# ecm.net
KiCad netlist of a schematic drawn in EAGLE
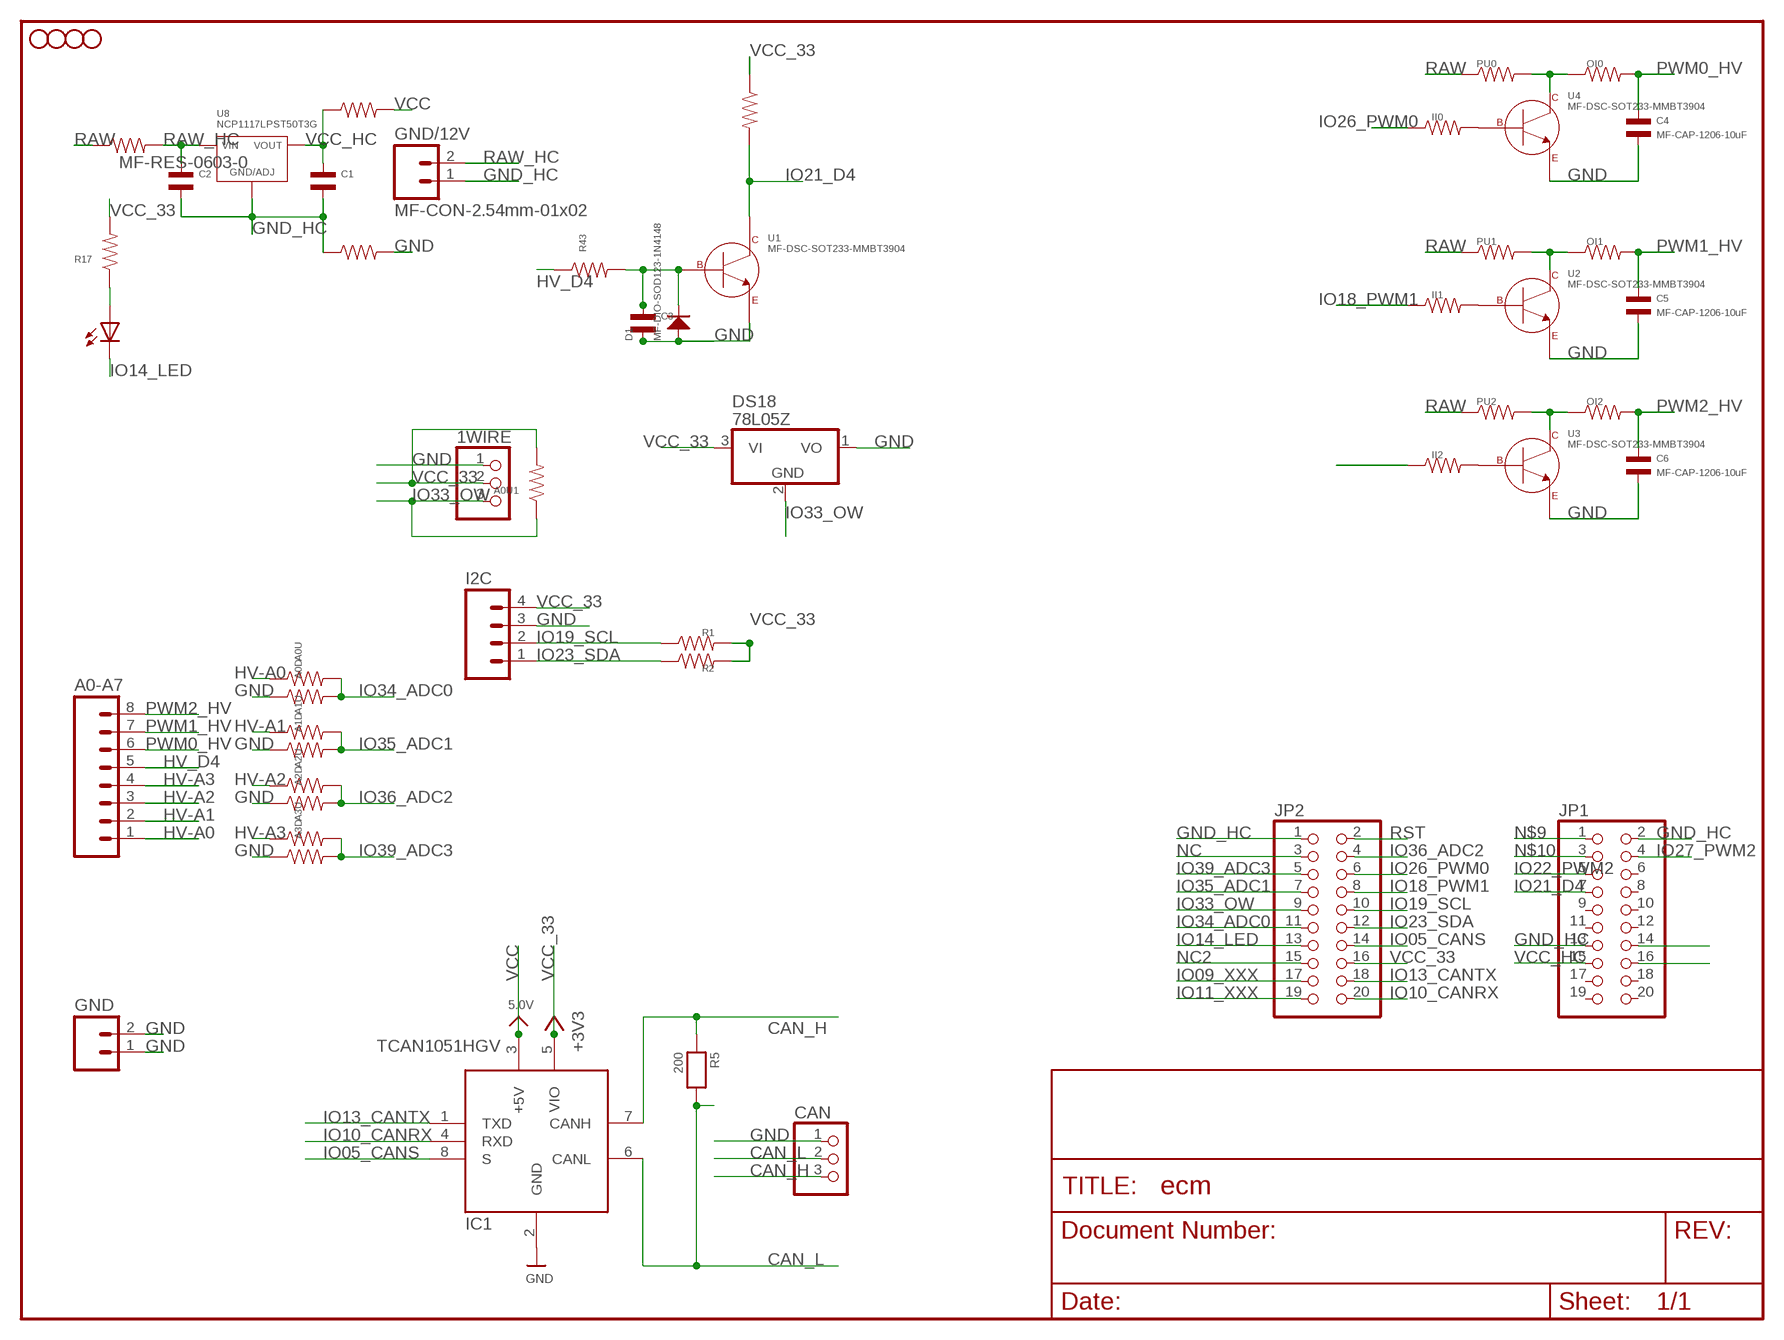
[diagram p0: schematic, sheet 1]

(export (version "E")
  (design (tool "Eeschema 10.0.6"))
  (components
    (comp (ref "1WIRE")
      (value "1WIRE")
      (footprint "eagle-import:1X03")
      (libsource (lib "eagle-import") (part "PINHD-1X3"))
    )
    (comp (ref "A0-A7")
      (value "MF-CON-2.54mm-01x08")
      (footprint "eagle-import:1X08")
      (libsource (lib "eagle-import") (part "M081X08"))
    )
    (comp (ref "A0D")
      (value "RESISTOR_1206")
      (footprint "eagle-import:R1206")
      (libsource (lib "eagle-import") (part "RESISTOR_1206"))
    )
    (comp (ref "A0U")
      (value "RESISTOR_1206")
      (footprint "eagle-import:R1206")
      (libsource (lib "eagle-import") (part "RESISTOR_1206"))
    )
    (comp (ref "A0U1")
      (value "RESISTOR_1206")
      (footprint "eagle-import:R1206")
      (libsource (lib "eagle-import") (part "RESISTOR_1206"))
    )
    (comp (ref "A1D")
      (value "RESISTOR_1206")
      (footprint "eagle-import:R1206")
      (libsource (lib "eagle-import") (part "RESISTOR_1206"))
    )
    (comp (ref "A1U")
      (value "RESISTOR_1206")
      (footprint "eagle-import:R1206")
      (libsource (lib "eagle-import") (part "RESISTOR_1206"))
    )
    (comp (ref "A2D")
      (value "RESISTOR_1206")
      (footprint "eagle-import:R1206")
      (libsource (lib "eagle-import") (part "RESISTOR_1206"))
    )
    (comp (ref "A2U")
      (value "RESISTOR_1206")
      (footprint "eagle-import:R1206")
      (libsource (lib "eagle-import") (part "RESISTOR_1206"))
    )
    (comp (ref "A3D")
      (value "RESISTOR_1206")
      (footprint "eagle-import:R1206")
      (libsource (lib "eagle-import") (part "RESISTOR_1206"))
    )
    (comp (ref "A3U")
      (value "RESISTOR_1206")
      (footprint "eagle-import:R1206")
      (libsource (lib "eagle-import") (part "RESISTOR_1206"))
    )
    (comp (ref "C1")
      (value "CAPACITOR_NP_1210")
      (footprint "eagle-import:C1210")
      (libsource (lib "eagle-import") (part "CAPACITOR_NP_1210"))
    )
    (comp (ref "C2")
      (value "CAPACITOR_NP_1210")
      (footprint "eagle-import:C1210")
      (libsource (lib "eagle-import") (part "CAPACITOR_NP_1210"))
    )
    (comp (ref "C3")
      (value "CAPACITOR_NP_1210")
      (footprint "eagle-import:C1210")
      (libsource (lib "eagle-import") (part "CAPACITOR_NP_1210"))
    )
    (comp (ref "C4")
      (value "MF-CAP-1206-10uF")
      (footprint "eagle-import:C1206")
      (libsource (lib "eagle-import") (part "CAPACITOR_NP_1206"))
    )
    (comp (ref "C5")
      (value "MF-CAP-1206-10uF")
      (footprint "eagle-import:C1206")
      (libsource (lib "eagle-import") (part "CAPACITOR_NP_1206"))
    )
    (comp (ref "C6")
      (value "MF-CAP-1206-10uF")
      (footprint "eagle-import:C1206")
      (libsource (lib "eagle-import") (part "CAPACITOR_NP_1206"))
    )
    (comp (ref "CAN")
      (value "PINHD-1X3")
      (footprint "eagle-import:1X03")
      (libsource (lib "eagle-import") (part "PINHD-1X3"))
    )
    (comp (ref "D1")
      (value "MF-DIO-SOD123-1N4148")
      (footprint "eagle-import:SOD-123")
      (fields (field (name "HOUSEPART") "YES"))
      (libsource (lib "eagle-import") (part "DIODES_SOD-123_1N4148"))
    )
    (comp (ref "D2")
      (value "RED")
      (footprint "eagle-import:LED-1206")
      (libsource (lib "eagle-import") (part "LED-RED1206"))
    )
    (comp (ref "DS18")
      (value "78L05Z")
      (footprint "eagle-import:TO92")
      (libsource (lib "eagle-import") (part "78ZL05"))
    )
    (comp (ref "GND")
      (value "MF-CON-2.54mm-01x02")
      (footprint "eagle-import:1X02")
      (libsource (lib "eagle-import") (part "M02PTH"))
    )
    (comp (ref "GND/12V")
      (value "MF-CON-2.54mm-01x02")
      (footprint "eagle-import:1X02")
      (libsource (lib "eagle-import") (part "M02PTH"))
    )
    (comp (ref "I2C")
      (value "PPPC041LFBN-RC")
      (footprint "eagle-import:1X04")
      (libsource (lib "eagle-import") (part "M04PTH"))
    )
    (comp (ref "IC1")
      (value "TCAN1051HGV")
      (footprint "eagle-import:SOIC8_150MIL")
      (libsource (lib "eagle-import") (part "CAN_TRANSCIEVER_TCAN1051V"))
    )
    (comp (ref "II0")
      (value "RESISTOR_1206")
      (footprint "eagle-import:R1206")
      (libsource (lib "eagle-import") (part "RESISTOR_1206"))
    )
    (comp (ref "II1")
      (value "RESISTOR_1206")
      (footprint "eagle-import:R1206")
      (libsource (lib "eagle-import") (part "RESISTOR_1206"))
    )
    (comp (ref "II2")
      (value "RESISTOR_1206")
      (footprint "eagle-import:R1206")
      (libsource (lib "eagle-import") (part "RESISTOR_1206"))
    )
    (comp (ref "JP1")
      (value "HEADER-2X10")
      (footprint "eagle-import:2X10")
      (libsource (lib "eagle-import") (part "HEADER-2X10"))
    )
    (comp (ref "JP2")
      (value "HEADER-2X10")
      (footprint "eagle-import:2X10")
      (libsource (lib "eagle-import") (part "HEADER-2X10"))
    )
    (comp (ref "OI0")
      (value "RESISTOR_1206")
      (footprint "eagle-import:R1206")
      (libsource (lib "eagle-import") (part "RESISTOR_1206"))
    )
    (comp (ref "OI1")
      (value "RESISTOR_1206")
      (footprint "eagle-import:R1206")
      (libsource (lib "eagle-import") (part "RESISTOR_1206"))
    )
    (comp (ref "OI2")
      (value "RESISTOR_1206")
      (footprint "eagle-import:R1206")
      (libsource (lib "eagle-import") (part "RESISTOR_1206"))
    )
    (comp (ref "PU0")
      (value "RESISTOR_1206")
      (footprint "eagle-import:R1206")
      (libsource (lib "eagle-import") (part "RESISTOR_1206"))
    )
    (comp (ref "PU1")
      (value "RESISTOR_1206")
      (footprint "eagle-import:R1206")
      (libsource (lib "eagle-import") (part "RESISTOR_1206"))
    )
    (comp (ref "PU2")
      (value "RESISTOR_1206")
      (footprint "eagle-import:R1206")
      (libsource (lib "eagle-import") (part "RESISTOR_1206"))
    )
    (comp (ref "R1")
      (value "RESISTOR_1206")
      (footprint "eagle-import:R1206")
      (libsource (lib "eagle-import") (part "RESISTOR_1206"))
    )
    (comp (ref "R2")
      (value "RESISTOR_1206")
      (footprint "eagle-import:R1206")
      (libsource (lib "eagle-import") (part "RESISTOR_1206"))
    )
    (comp (ref "R5")
      (value "200")
      (footprint "eagle-import:1206")
      (libsource (lib "eagle-import") (part "microbuilder_RESISTOR1206"))
    )
    (comp (ref "R17")
      (value "RESISTOR_1206")
      (footprint "eagle-import:R1206")
      (libsource (lib "eagle-import") (part "RESISTOR_1206"))
    )
    (comp (ref "R43")
      (value "RESISTOR_1206")
      (footprint "eagle-import:R1206")
      (libsource (lib "eagle-import") (part "RESISTOR_1206"))
    )
    (comp (ref "R45")
      (value "RESISTOR_1206")
      (footprint "eagle-import:R1206")
      (libsource (lib "eagle-import") (part "RESISTOR_1206"))
    )
    (comp (ref "RIN7")
      (value "MF-RES-0603-0")
      (footprint "eagle-import:1206")
      (libsource (lib "eagle-import") (part "RESISTOR1206"))
    )
    (comp (ref "RIN8")
      (value "MF-RES-0603-0")
      (footprint "eagle-import:1206")
      (libsource (lib "eagle-import") (part "RESISTOR1206"))
    )
    (comp (ref "RIN19")
      (value "MF-RES-0603-0")
      (footprint "eagle-import:1206")
      (libsource (lib "eagle-import") (part "RESISTOR1206"))
    )
    (comp (ref "STANDOFF2")
      (value "STAND-OFF")
      (footprint "eagle-import:STAND-OFF")
      (libsource (lib "eagle-import") (part "STAND-OFF"))
    )
    (comp (ref "STANDOFF3")
      (value "STAND-OFF")
      (footprint "eagle-import:STAND-OFF")
      (libsource (lib "eagle-import") (part "STAND-OFF"))
    )
    (comp (ref "STANDOFF4")
      (value "STAND-OFF")
      (footprint "eagle-import:STAND-OFF")
      (libsource (lib "eagle-import") (part "STAND-OFF"))
    )
    (comp (ref "STANDOFF5")
      (value "STAND-OFF")
      (footprint "eagle-import:STAND-OFF")
      (libsource (lib "eagle-import") (part "STAND-OFF"))
    )
    (comp (ref "U1")
      (value "MF-DSC-SOT233-MMBT3904")
      (footprint "eagle-import:SOT-23-3")
      (fields (field (name "HOUSEPART") "YES"))
      (libsource (lib "eagle-import") (part "NPN_BJT_SOT-23-3MMBT3904"))
    )
    (comp (ref "U2")
      (value "MF-DSC-SOT233-MMBT3904")
      (footprint "eagle-import:SOT-23-3")
      (fields (field (name "HOUSEPART") "YES"))
      (libsource (lib "eagle-import") (part "NPN_BJT_SOT-23-3MMBT3904"))
    )
    (comp (ref "U3")
      (value "MF-DSC-SOT233-MMBT3904")
      (footprint "eagle-import:SOT-23-3")
      (fields (field (name "HOUSEPART") "YES"))
      (libsource (lib "eagle-import") (part "NPN_BJT_SOT-23-3MMBT3904"))
    )
    (comp (ref "U4")
      (value "MF-DSC-SOT233-MMBT3904")
      (footprint "eagle-import:SOT-23-3")
      (fields (field (name "HOUSEPART") "YES"))
      (libsource (lib "eagle-import") (part "NPN_BJT_SOT-23-3MMBT3904"))
    )
    (comp (ref "U8")
      (value "NCP1117LPST50T3G")
      (footprint "eagle-import:SOT-223-3")
      (fields (field (name "HOUSEPART") "NO"))
      (libsource (lib "eagle-import") (part "NCP1117LPST50T3G"))
    )
  )
  (nets
    (net (code "1") (name "+3V3") (class "Default")
      (node (ref "1WIRE") (pin "2") (pinfunction "2_2") (pintype "passive"))
      (node (ref "A0U1") (pin "P$2") (pinfunction "P$2_P$2") (pintype "passive"))
      (node (ref "DS18") (pin "3") (pinfunction "VI_3") (pintype "input"))
      (node (ref "I2C") (pin "4") (pinfunction "4_4") (pintype "passive"))
      (node (ref "IC1") (pin "5") (pinfunction "VIO_5") (pintype "power_in"))
      (node (ref "JP2") (pin "16") (pinfunction "16_16") (pintype "passive"))
      (node (ref "R1") (pin "P$2") (pinfunction "P$2_P$2") (pintype "passive"))
      (node (ref "R17") (pin "P$2") (pinfunction "P$2_P$2") (pintype "passive"))
      (node (ref "R2") (pin "P$2") (pinfunction "P$2_P$2") (pintype "passive"))
      (node (ref "R45") (pin "P$1") (pinfunction "P$1_P$1") (pintype "passive"))
    )
    (net (code "2") (name "/CAN_H") (class "Default")
      (node (ref "CAN") (pin "3") (pinfunction "3_3") (pintype "passive"))
      (node (ref "IC1") (pin "7") (pinfunction "CANH_7") (pintype "bidirectional"))
      (node (ref "R5") (pin "1") (pinfunction "1_1") (pintype "passive"))
    )
    (net (code "3") (name "/CAN_L") (class "Default")
      (node (ref "CAN") (pin "2") (pinfunction "2_2") (pintype "passive"))
      (node (ref "IC1") (pin "6") (pinfunction "CANL_6") (pintype "bidirectional"))
      (node (ref "R5") (pin "2") (pinfunction "2_2") (pintype "passive"))
    )
    (net (code "4") (name "/GND_HC") (class "Default")
      (node (ref "C1") (pin "P$2") (pinfunction "P$2_P$2") (pintype "passive"))
      (node (ref "C2") (pin "P$2") (pinfunction "P$2_P$2") (pintype "passive"))
      (node (ref "GND/12V") (pin "1") (pinfunction "1_1") (pintype "passive"))
      (node (ref "JP1") (pin "13") (pinfunction "13_13") (pintype "passive"))
      (node (ref "JP1") (pin "2") (pinfunction "2_2") (pintype "passive"))
      (node (ref "JP2") (pin "1") (pinfunction "1_1") (pintype "passive"))
      (node (ref "RIN8") (pin "1") (pinfunction "1_1") (pintype "passive"))
      (node (ref "U8") (pin "P$2") (pinfunction "GND/ADJ_P$2") (pintype "bidirectional"))
    )
    (net (code "5") (name "/HV-A0") (class "Default")
      (node (ref "A0-A7") (pin "1") (pinfunction "1_1") (pintype "passive"))
      (node (ref "A0U") (pin "P$1") (pinfunction "P$1_P$1") (pintype "passive"))
    )
    (net (code "6") (name "/HV-A1") (class "Default")
      (node (ref "A0-A7") (pin "2") (pinfunction "2_2") (pintype "passive"))
      (node (ref "A1U") (pin "P$1") (pinfunction "P$1_P$1") (pintype "passive"))
    )
    (net (code "7") (name "/HV-A2") (class "Default")
      (node (ref "A0-A7") (pin "3") (pinfunction "3_3") (pintype "passive"))
      (node (ref "A2U") (pin "P$1") (pinfunction "P$1_P$1") (pintype "passive"))
    )
    (net (code "8") (name "/HV-A3") (class "Default")
      (node (ref "A0-A7") (pin "4") (pinfunction "4_4") (pintype "passive"))
      (node (ref "A3U") (pin "P$1") (pinfunction "P$1_P$1") (pintype "passive"))
    )
    (net (code "9") (name "/HV_D4") (class "Default")
      (node (ref "A0-A7") (pin "5") (pinfunction "5_5") (pintype "passive"))
      (node (ref "R43") (pin "P$1") (pinfunction "P$1_P$1") (pintype "passive"))
    )
    (net (code "10") (name "/IO05_CANS") (class "Default")
      (node (ref "IC1") (pin "8") (pinfunction "S_8") (pintype "input"))
      (node (ref "JP2") (pin "14") (pinfunction "14_14") (pintype "passive"))
    )
    (net (code "11") (name "/IO09_XXX") (class "Default")
      (node (ref "JP2") (pin "17") (pinfunction "17_17") (pintype "passive"))
    )
    (net (code "12") (name "/IO10_CANRX") (class "Default")
      (node (ref "IC1") (pin "4") (pinfunction "RXD_4") (pintype "output"))
      (node (ref "JP2") (pin "20") (pinfunction "20_20") (pintype "passive"))
    )
    (net (code "13") (name "/IO11_XXX") (class "Default")
      (node (ref "JP2") (pin "19") (pinfunction "19_19") (pintype "passive"))
    )
    (net (code "14") (name "/IO13_CANTX") (class "Default")
      (node (ref "IC1") (pin "1") (pinfunction "TXD_1") (pintype "input"))
      (node (ref "JP2") (pin "18") (pinfunction "18_18") (pintype "passive"))
    )
    (net (code "15") (name "/IO14_LED") (class "Default")
      (node (ref "D2") (pin "C") (pinfunction "C_C") (pintype "passive"))
      (node (ref "JP2") (pin "13") (pinfunction "13_13") (pintype "passive"))
    )
    (net (code "16") (name "/IO18_PWM1") (class "Default")
      (node (ref "II1") (pin "P$1") (pinfunction "P$1_P$1") (pintype "passive"))
      (node (ref "JP2") (pin "8") (pinfunction "8_8") (pintype "passive"))
    )
    (net (code "17") (name "/IO19_SCL") (class "Default")
      (node (ref "I2C") (pin "2") (pinfunction "2_2") (pintype "passive"))
      (node (ref "JP2") (pin "10") (pinfunction "10_10") (pintype "passive"))
      (node (ref "R1") (pin "P$1") (pinfunction "P$1_P$1") (pintype "passive"))
    )
    (net (code "18") (name "/IO21_D4") (class "Default")
      (node (ref "JP1") (pin "7") (pinfunction "7_7") (pintype "passive"))
      (node (ref "R45") (pin "P$2") (pinfunction "P$2_P$2") (pintype "passive"))
      (node (ref "U1") (pin "P$3") (pinfunction "COLLECTOR_P$3") (pintype "bidirectional"))
    )
    (net (code "19") (name "/IO22_PWM2") (class "Default")
      (node (ref "II2") (pin "P$1") (pinfunction "P$1_P$1") (pintype "passive"))
      (node (ref "JP1") (pin "5") (pinfunction "5_5") (pintype "passive"))
    )
    (net (code "20") (name "/IO23_SDA") (class "Default")
      (node (ref "I2C") (pin "1") (pinfunction "1_1") (pintype "passive"))
      (node (ref "JP2") (pin "12") (pinfunction "12_12") (pintype "passive"))
      (node (ref "R2") (pin "P$1") (pinfunction "P$1_P$1") (pintype "passive"))
    )
    (net (code "21") (name "/IO26_PWM0") (class "Default")
      (node (ref "II0") (pin "P$1") (pinfunction "P$1_P$1") (pintype "passive"))
      (node (ref "JP2") (pin "6") (pinfunction "6_6") (pintype "passive"))
    )
    (net (code "22") (name "/IO27_PWM2") (class "Default")
      (node (ref "JP1") (pin "4") (pinfunction "4_4") (pintype "passive"))
    )
    (net (code "23") (name "/IO33_OW") (class "Default")
      (node (ref "1WIRE") (pin "3") (pinfunction "3_3") (pintype "passive"))
      (node (ref "A0U1") (pin "P$1") (pinfunction "P$1_P$1") (pintype "passive"))
      (node (ref "DS18") (pin "2") (pinfunction "GND_2") (pintype "passive"))
      (node (ref "JP2") (pin "9") (pinfunction "9_9") (pintype "passive"))
    )
    (net (code "24") (name "/IO34_ADC0") (class "Default")
      (node (ref "A0D") (pin "P$2") (pinfunction "P$2_P$2") (pintype "passive"))
      (node (ref "A0U") (pin "P$2") (pinfunction "P$2_P$2") (pintype "passive"))
      (node (ref "JP2") (pin "11") (pinfunction "11_11") (pintype "passive"))
    )
    (net (code "25") (name "/IO35_ADC1") (class "Default")
      (node (ref "A1D") (pin "P$2") (pinfunction "P$2_P$2") (pintype "passive"))
      (node (ref "A1U") (pin "P$2") (pinfunction "P$2_P$2") (pintype "passive"))
      (node (ref "JP2") (pin "7") (pinfunction "7_7") (pintype "passive"))
    )
    (net (code "26") (name "/IO36_ADC2") (class "Default")
      (node (ref "A2D") (pin "P$2") (pinfunction "P$2_P$2") (pintype "passive"))
      (node (ref "A2U") (pin "P$2") (pinfunction "P$2_P$2") (pintype "passive"))
      (node (ref "JP2") (pin "4") (pinfunction "4_4") (pintype "passive"))
    )
    (net (code "27") (name "/IO39_ADC3") (class "Default")
      (node (ref "A3D") (pin "P$2") (pinfunction "P$2_P$2") (pintype "passive"))
      (node (ref "A3U") (pin "P$2") (pinfunction "P$2_P$2") (pintype "passive"))
      (node (ref "JP2") (pin "5") (pinfunction "5_5") (pintype "passive"))
    )
    (net (code "28") (name "/N$9") (class "Default")
      (node (ref "JP1") (pin "1") (pinfunction "1_1") (pintype "passive"))
    )
    (net (code "29") (name "/N$10") (class "Default")
      (node (ref "JP1") (pin "3") (pinfunction "3_3") (pintype "passive"))
    )
    (net (code "30") (name "/NC") (class "Default")
      (node (ref "JP2") (pin "3") (pinfunction "3_3") (pintype "passive"))
    )
    (net (code "31") (name "/NC2") (class "Default")
      (node (ref "JP2") (pin "15") (pinfunction "15_15") (pintype "passive"))
    )
    (net (code "32") (name "/PWM0_HV") (class "Default")
      (node (ref "A0-A7") (pin "6") (pinfunction "6_6") (pintype "passive"))
      (node (ref "C4") (pin "P$1") (pinfunction "P$1_P$1") (pintype "passive"))
      (node (ref "OI0") (pin "P$2") (pinfunction "P$2_P$2") (pintype "passive"))
    )
    (net (code "33") (name "/PWM1_HV") (class "Default")
      (node (ref "A0-A7") (pin "7") (pinfunction "7_7") (pintype "passive"))
      (node (ref "C5") (pin "P$1") (pinfunction "P$1_P$1") (pintype "passive"))
      (node (ref "OI1") (pin "P$2") (pinfunction "P$2_P$2") (pintype "passive"))
    )
    (net (code "34") (name "/PWM2_HV") (class "Default")
      (node (ref "A0-A7") (pin "8") (pinfunction "8_8") (pintype "passive"))
      (node (ref "C6") (pin "P$1") (pinfunction "P$1_P$1") (pintype "passive"))
      (node (ref "OI2") (pin "P$2") (pinfunction "P$2_P$2") (pintype "passive"))
    )
    (net (code "35") (name "/RAW") (class "Default")
      (node (ref "PU0") (pin "P$1") (pinfunction "P$1_P$1") (pintype "passive"))
      (node (ref "PU1") (pin "P$1") (pinfunction "P$1_P$1") (pintype "passive"))
      (node (ref "PU2") (pin "P$1") (pinfunction "P$1_P$1") (pintype "passive"))
      (node (ref "RIN19") (pin "1") (pinfunction "1_1") (pintype "passive"))
    )
    (net (code "36") (name "/RAW_HC") (class "Default")
      (node (ref "C2") (pin "P$1") (pinfunction "P$1_P$1") (pintype "passive"))
      (node (ref "GND/12V") (pin "2") (pinfunction "2_2") (pintype "passive"))
      (node (ref "RIN19") (pin "2") (pinfunction "2_2") (pintype "passive"))
      (node (ref "U8") (pin "P$4") (pinfunction "VIN_P$4") (pintype "bidirectional"))
    )
    (net (code "37") (name "/RST") (class "Default")
      (node (ref "JP2") (pin "2") (pinfunction "2_2") (pintype "passive"))
    )
    (net (code "38") (name "/VCC_HC") (class "Default")
      (node (ref "C1") (pin "P$1") (pinfunction "P$1_P$1") (pintype "passive"))
      (node (ref "JP1") (pin "15") (pinfunction "15_15") (pintype "passive"))
      (node (ref "RIN7") (pin "1") (pinfunction "1_1") (pintype "passive"))
      (node (ref "U8") (pin "P$1") (pinfunction "VOUT_P$1") (pintype "bidirectional"))
      (node (ref "U8") (pin "P$3") (pinfunction "VOUT_P$3") (pintype "bidirectional"))
    )
    (net (code "39") (name "5.0V") (class "Default")
      (node (ref "IC1") (pin "3") (pinfunction "+5V_3") (pintype "power_in"))
      (node (ref "RIN7") (pin "2") (pinfunction "2_2") (pintype "passive"))
    )
    (net (code "40") (name "GND") (class "Default")
      (node (ref "1WIRE") (pin "1") (pinfunction "1_1") (pintype "passive"))
      (node (ref "A0D") (pin "P$1") (pinfunction "P$1_P$1") (pintype "passive"))
      (node (ref "A1D") (pin "P$1") (pinfunction "P$1_P$1") (pintype "passive"))
      (node (ref "A2D") (pin "P$1") (pinfunction "P$1_P$1") (pintype "passive"))
      (node (ref "A3D") (pin "P$1") (pinfunction "P$1_P$1") (pintype "passive"))
      (node (ref "C3") (pin "P$2") (pinfunction "P$2_P$2") (pintype "passive"))
      (node (ref "C4") (pin "P$2") (pinfunction "P$2_P$2") (pintype "passive"))
      (node (ref "C5") (pin "P$2") (pinfunction "P$2_P$2") (pintype "passive"))
      (node (ref "C6") (pin "P$2") (pinfunction "P$2_P$2") (pintype "passive"))
      (node (ref "CAN") (pin "1") (pinfunction "1_1") (pintype "passive"))
      (node (ref "D1") (pin "ANODE") (pinfunction "ANODE_ANODE") (pintype "bidirectional"))
      (node (ref "DS18") (pin "1") (pinfunction "VO_1") (pintype "passive"))
      (node (ref "GND") (pin "1") (pinfunction "1_1") (pintype "passive"))
      (node (ref "GND") (pin "2") (pinfunction "2_2") (pintype "passive"))
      (node (ref "I2C") (pin "3") (pinfunction "3_3") (pintype "passive"))
      (node (ref "IC1") (pin "2") (pinfunction "GND_2") (pintype "power_in"))
      (node (ref "RIN8") (pin "2") (pinfunction "2_2") (pintype "passive"))
      (node (ref "U1") (pin "P$2") (pinfunction "EMITTER_P$2") (pintype "bidirectional"))
      (node (ref "U2") (pin "P$2") (pinfunction "EMITTER_P$2") (pintype "bidirectional"))
      (node (ref "U3") (pin "P$2") (pinfunction "EMITTER_P$2") (pintype "bidirectional"))
      (node (ref "U4") (pin "P$2") (pinfunction "EMITTER_P$2") (pintype "bidirectional"))
    )
    (net (code "41") (name "Net-(D2-PadA)") (class "Default")
      (node (ref "D2") (pin "A") (pinfunction "A_A") (pintype "passive"))
      (node (ref "R17") (pin "P$1") (pinfunction "P$1_P$1") (pintype "passive"))
    )
    (net (code "42") (name "Net-(U1-BASE)") (class "Default")
      (node (ref "C3") (pin "P$1") (pinfunction "P$1_P$1") (pintype "passive"))
      (node (ref "D1") (pin "CATHODE") (pinfunction "CATHODE_CATHODE") (pintype "bidirectional"))
      (node (ref "R43") (pin "P$2") (pinfunction "P$2_P$2") (pintype "passive"))
      (node (ref "U1") (pin "P$1") (pinfunction "BASE_P$1") (pintype "bidirectional"))
    )
    (net (code "43") (name "Net-(U2-BASE)") (class "Default")
      (node (ref "II1") (pin "P$2") (pinfunction "P$2_P$2") (pintype "passive"))
      (node (ref "U2") (pin "P$1") (pinfunction "BASE_P$1") (pintype "bidirectional"))
    )
    (net (code "44") (name "Net-(U2-COLLECTOR)") (class "Default")
      (node (ref "OI1") (pin "P$1") (pinfunction "P$1_P$1") (pintype "passive"))
      (node (ref "PU1") (pin "P$2") (pinfunction "P$2_P$2") (pintype "passive"))
      (node (ref "U2") (pin "P$3") (pinfunction "COLLECTOR_P$3") (pintype "bidirectional"))
    )
    (net (code "45") (name "Net-(U3-BASE)") (class "Default")
      (node (ref "II2") (pin "P$2") (pinfunction "P$2_P$2") (pintype "passive"))
      (node (ref "U3") (pin "P$1") (pinfunction "BASE_P$1") (pintype "bidirectional"))
    )
    (net (code "46") (name "Net-(U3-COLLECTOR)") (class "Default")
      (node (ref "OI2") (pin "P$1") (pinfunction "P$1_P$1") (pintype "passive"))
      (node (ref "PU2") (pin "P$2") (pinfunction "P$2_P$2") (pintype "passive"))
      (node (ref "U3") (pin "P$3") (pinfunction "COLLECTOR_P$3") (pintype "bidirectional"))
    )
    (net (code "47") (name "Net-(U4-BASE)") (class "Default")
      (node (ref "II0") (pin "P$2") (pinfunction "P$2_P$2") (pintype "passive"))
      (node (ref "U4") (pin "P$1") (pinfunction "BASE_P$1") (pintype "bidirectional"))
    )
    (net (code "48") (name "Net-(U4-COLLECTOR)") (class "Default")
      (node (ref "OI0") (pin "P$1") (pinfunction "P$1_P$1") (pintype "passive"))
      (node (ref "PU0") (pin "P$2") (pinfunction "P$2_P$2") (pintype "passive"))
      (node (ref "U4") (pin "P$3") (pinfunction "COLLECTOR_P$3") (pintype "bidirectional"))
    )
    (net (code "49") (name "unconnected-(JP1-Pad6)") (class "Default")
      (node (ref "JP1") (pin "6") (pinfunction "6_6") (pintype "passive"))
    )
    (net (code "50") (name "unconnected-(JP1-Pad8)") (class "Default")
      (node (ref "JP1") (pin "8") (pinfunction "8_8") (pintype "passive"))
    )
    (net (code "51") (name "unconnected-(JP1-Pad9)") (class "Default")
      (node (ref "JP1") (pin "9") (pinfunction "9_9") (pintype "passive"))
    )
    (net (code "52") (name "unconnected-(JP1-Pad10)") (class "Default")
      (node (ref "JP1") (pin "10") (pinfunction "10_10") (pintype "passive"))
    )
    (net (code "53") (name "unconnected-(JP1-Pad11)") (class "Default")
      (node (ref "JP1") (pin "11") (pinfunction "11_11") (pintype "passive"))
    )
    (net (code "54") (name "unconnected-(JP1-Pad12)") (class "Default")
      (node (ref "JP1") (pin "12") (pinfunction "12_12") (pintype "passive"))
    )
    (net (code "55") (name "unconnected-(JP1-Pad14)") (class "Default")
      (node (ref "JP1") (pin "14") (pinfunction "14_14") (pintype "passive"))
    )
    (net (code "56") (name "unconnected-(JP1-Pad16)") (class "Default")
      (node (ref "JP1") (pin "16") (pinfunction "16_16") (pintype "passive"))
    )
    (net (code "57") (name "unconnected-(JP1-Pad17)") (class "Default")
      (node (ref "JP1") (pin "17") (pinfunction "17_17") (pintype "passive"))
    )
    (net (code "58") (name "unconnected-(JP1-Pad18)") (class "Default")
      (node (ref "JP1") (pin "18") (pinfunction "18_18") (pintype "passive"))
    )
    (net (code "59") (name "unconnected-(JP1-Pad19)") (class "Default")
      (node (ref "JP1") (pin "19") (pinfunction "19_19") (pintype "passive"))
    )
    (net (code "60") (name "unconnected-(JP1-Pad20)") (class "Default")
      (node (ref "JP1") (pin "20") (pinfunction "20_20") (pintype "passive"))
    )
  )
)
